# STM32F407VG.net
KiCad netlist of a schematic drawn in Altium Designer
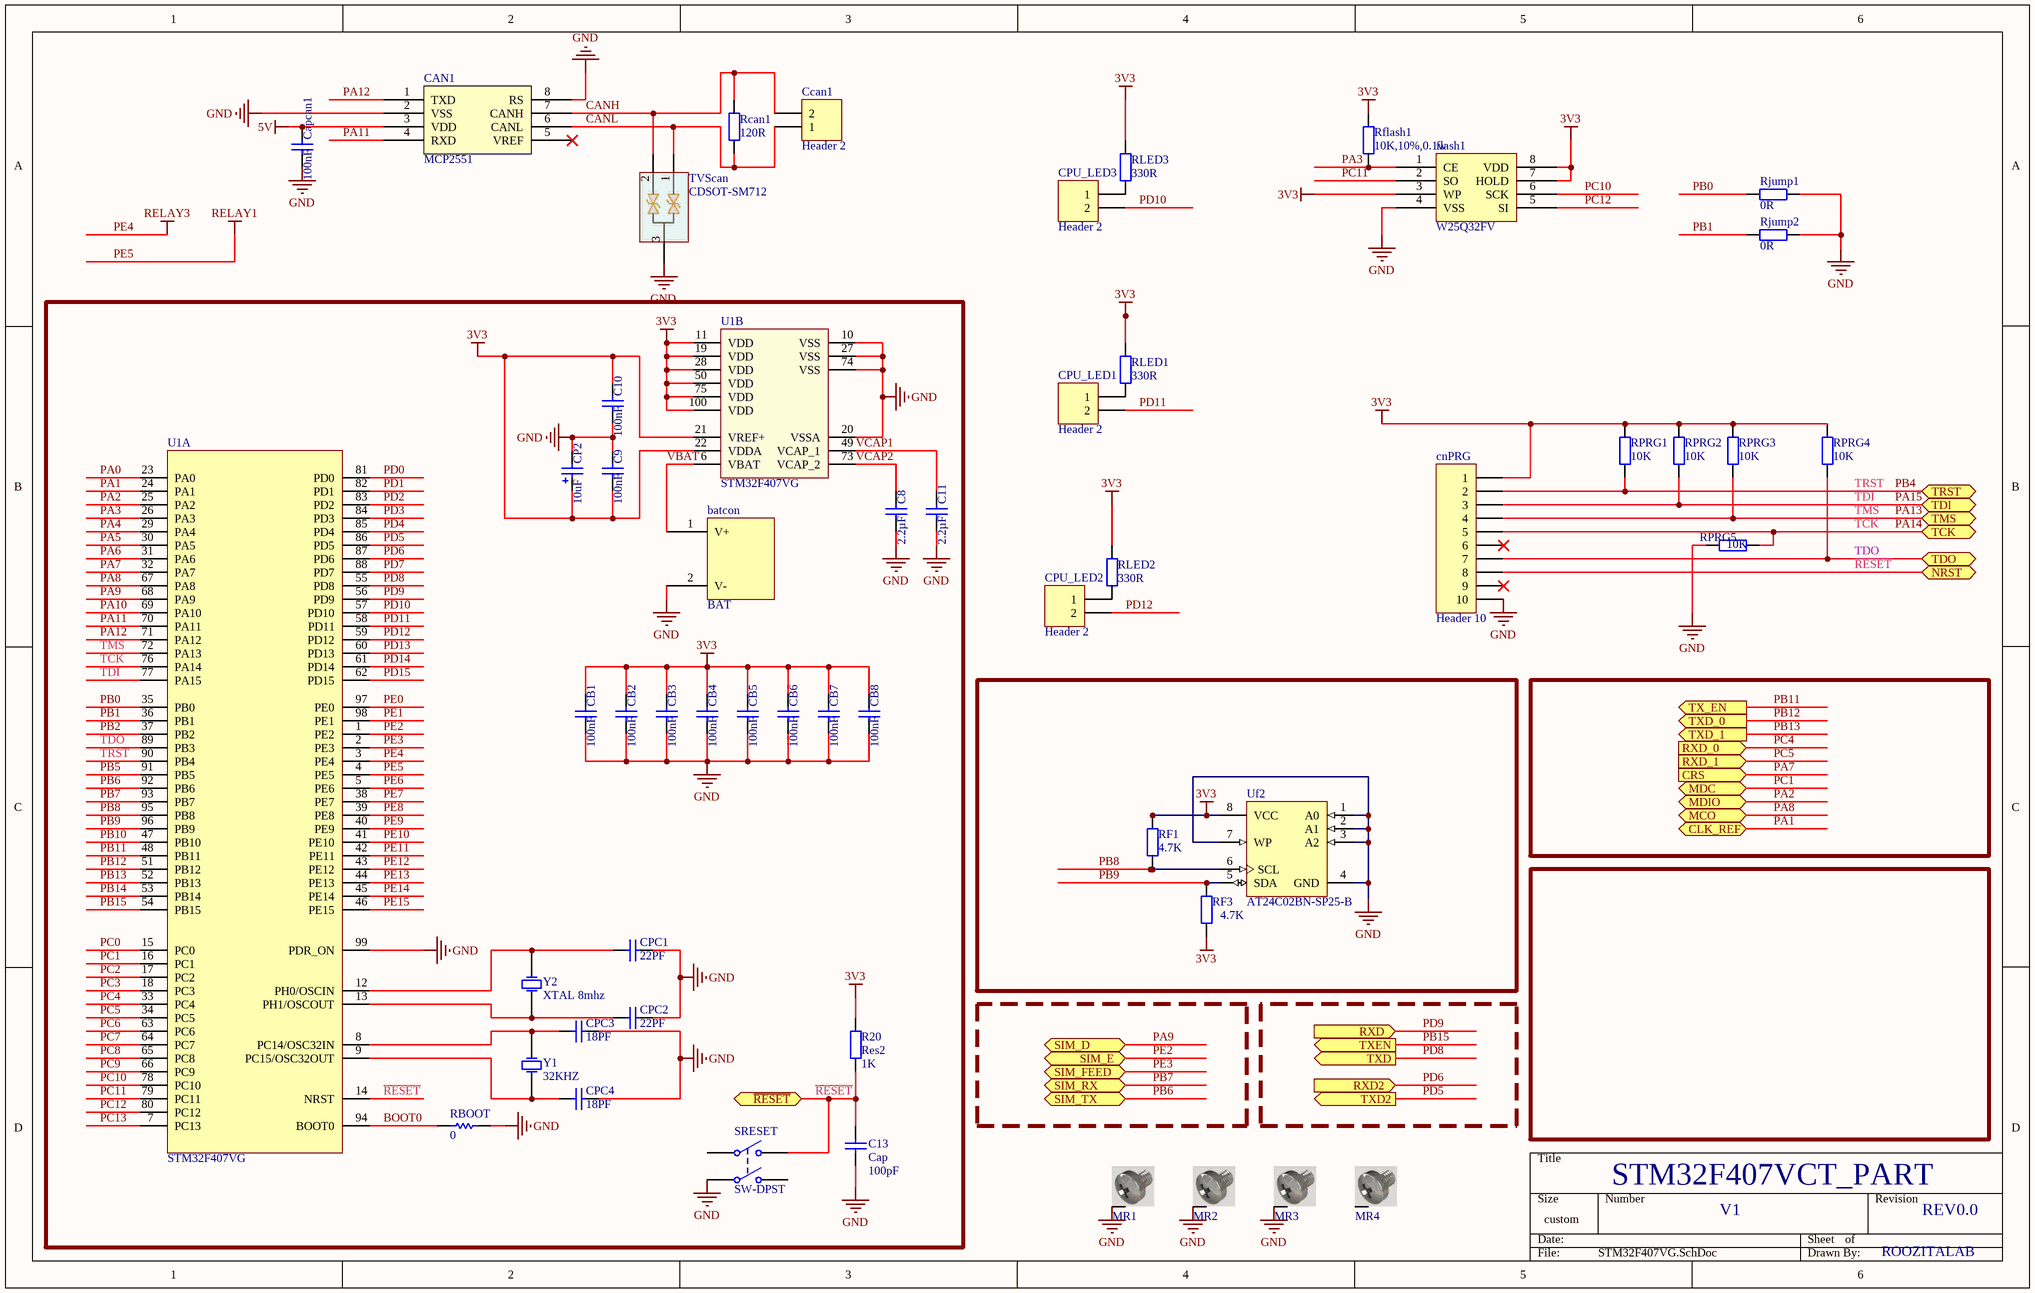
[diagram p0: STM32F407VG.SchDoc]

(export (version "E")
  (design (tool "Eeschema 10.0.6"))
  (components
    (comp (ref "batcon") (value "BAT") (footprint "BATTERY") (libsource (lib "my dxp lib") (part "BAT")))
    (comp (ref "C8")
      (value "2.2µF")
      (footprint "0805.")
      (description "Capacitor")
      (fields (field (name "PUBLISHER") "Altium Limited"))
      (libsource (lib "STM32F407_144") (part "Cap"))
    )
    (comp (ref "C9")
      (value "100nF")
      (footprint "0805.")
      (description "Capacitor")
      (fields (field (name "PUBLISHER") "Altium Limited"))
      (libsource (lib "STM32F407_144") (part "Cap"))
    )
    (comp (ref "C10")
      (value "100nF")
      (footprint "0805.")
      (description "Capacitor")
      (fields (field (name "PUBLISHER") "Altium Limited"))
      (libsource (lib "STM32F407_144") (part "Cap"))
    )
    (comp (ref "C11")
      (value "2.2µF")
      (footprint "0805.")
      (description "Capacitor")
      (fields (field (name "PUBLISHER") "Altium Limited"))
      (libsource (lib "STM32F407_144") (part "Cap"))
    )
    (comp (ref "C13")
      (value "Cap")
      (footprint "0805.")
      (description "Capacitor")
      (fields (field (name "ALTIUM_VALUE") "100pF") (field (name "PUBLISHER") "Altium Limited"))
      (libsource (lib "Miscellaneous Devices") (part "Cap"))
    )
    (comp (ref "CAN1")
      (value "MCP2551")
      (footprint "SOIC8")
      (libsource (lib "PCB_Project1") (part "SN65VHD230"))
    )
    (comp (ref "Capcan1")
      (value "100nF")
      (footprint "0805.")
      (description "Capacitor")
      (fields (field (name "PUBLISHER") "Altium Limited"))
      (libsource (lib "STM32F407_144") (part "Cap"))
    )
    (comp (ref "CB1")
      (value "100nF")
      (footprint "0805.")
      (description "Capacitor")
      (fields (field (name "PUBLISHER") "Altium Limited"))
      (libsource (lib "STM32F407_144") (part "Cap"))
    )
    (comp (ref "CB2")
      (value "100nF")
      (footprint "0805.")
      (description "Capacitor")
      (fields (field (name "PUBLISHER") "Altium Limited"))
      (libsource (lib "STM32F407_144") (part "Cap"))
    )
    (comp (ref "CB3")
      (value "100nF")
      (footprint "0805.")
      (description "Capacitor")
      (fields (field (name "PUBLISHER") "Altium Limited"))
      (libsource (lib "STM32F407_144") (part "Cap"))
    )
    (comp (ref "CB4")
      (value "100nF")
      (footprint "0805.")
      (description "Capacitor")
      (fields (field (name "PUBLISHER") "Altium Limited"))
      (libsource (lib "STM32F407_144") (part "Cap"))
    )
    (comp (ref "CB5")
      (value "100nF")
      (footprint "0805.")
      (description "Capacitor")
      (fields (field (name "PUBLISHER") "Altium Limited"))
      (libsource (lib "STM32F407_144") (part "Cap"))
    )
    (comp (ref "CB6")
      (value "100nF")
      (footprint "0805.")
      (description "Capacitor")
      (fields (field (name "PUBLISHER") "Altium Limited"))
      (libsource (lib "STM32F407_144") (part "Cap"))
    )
    (comp (ref "CB7")
      (value "100nF")
      (footprint "0805.")
      (description "Capacitor")
      (fields (field (name "PUBLISHER") "Altium Limited"))
      (libsource (lib "STM32F407_144") (part "Cap"))
    )
    (comp (ref "CB8")
      (value "100nF")
      (footprint "0805.")
      (description "Capacitor")
      (fields (field (name "PUBLISHER") "Altium Limited"))
      (libsource (lib "STM32F407_144") (part "Cap"))
    )
    (comp (ref "Ccan1")
      (value "Header 2")
      (footprint "HDR1X2")
      (description "Header, 2-Pin")
      (fields (field (name "PUBLISHER") "Altium Limited"))
      (libsource (lib "") (part "Header 2_1"))
    )
    (comp (ref "cnPRG")
      (value "Header 10")
      (footprint "HDR1X10")
      (description "Header, 10-Pin")
      (fields (field (name "PUBLISHER") "Altium Limited"))
      (libsource (lib "Miscellaneous Connectors") (part "Header 10"))
    )
    (comp (ref "CP2")
      (value "10uF")
      (footprint "C1206.")
      (description "Polarized Capacitor (Radial)")
      (fields (field (name "PUBLISHER") "Altium Limited"))
      (libsource (lib "STM32F407_144") (part "Cap Pol1"))
    )
    (comp (ref "CPC1")
      (value "22PF")
      (footprint "0805.")
      (description "Capacitor")
      (fields (field (name "PUBLISHER") "Altium Limited"))
      (libsource (lib "STM32F407VG") (part "Cap"))
    )
    (comp (ref "CPC2")
      (value "22PF")
      (footprint "0805.")
      (description "Capacitor")
      (fields (field (name "PUBLISHER") "Altium Limited"))
      (libsource (lib "STM32F407VG") (part "Cap"))
    )
    (comp (ref "CPC3")
      (value "18PF")
      (footprint "0805.")
      (description "Capacitor")
      (fields (field (name "PUBLISHER") "Altium Limited"))
      (libsource (lib "STM32F407VG") (part "Cap"))
    )
    (comp (ref "CPC4")
      (value "18PF")
      (footprint "0805.")
      (description "Capacitor")
      (fields (field (name "PUBLISHER") "Altium Limited"))
      (libsource (lib "STM32F407VG") (part "Cap"))
    )
    (comp (ref "CPU_LED1")
      (value "Header 2")
      (footprint "HDR1X2")
      (description "Header, 2-Pin")
      (fields (field (name "PUBLISHER") "Altium Limited"))
      (libsource (lib "Miscellaneous Connectors") (part "Header 2"))
    )
    (comp (ref "CPU_LED2")
      (value "Header 2")
      (footprint "HDR1X2")
      (description "Header, 2-Pin")
      (fields (field (name "PUBLISHER") "Altium Limited"))
      (libsource (lib "Miscellaneous Connectors") (part "Header 2"))
    )
    (comp (ref "CPU_LED3")
      (value "Header 2")
      (footprint "HDR1X2")
      (description "Header, 2-Pin")
      (fields (field (name "PUBLISHER") "Altium Limited"))
      (libsource (lib "Miscellaneous Connectors") (part "Header 2"))
    )
    (comp (ref "flash1")
      (value "W25Q32FV")
      (footprint "SOIC8")
      (libsource (lib "PCB_Project1") (part "SST25"))
    )
    (comp (ref "MR1")
      (value "Screw")
      (footprint "Board Screw")
      (description "Board Screw With Spacer")
      (libsource (lib "My Library") (part "Board Screw"))
    )
    (comp (ref "MR2")
      (value "Screw")
      (footprint "Board Screw")
      (description "Board Screw With Spacer")
      (libsource (lib "My Library") (part "Board Screw"))
    )
    (comp (ref "MR3")
      (value "Screw")
      (footprint "Board Screw")
      (description "Board Screw With Spacer")
      (libsource (lib "My Library") (part "Board Screw"))
    )
    (comp (ref "MR4")
      (value "Screw")
      (footprint "Board Screw")
      (description "Board Screw With Spacer")
      (libsource (lib "My Library") (part "Board Screw"))
    )
    (comp (ref "R20")
      (value "Res2")
      (footprint "0805.")
      (description "Resistor")
      (fields (field (name "ALTIUM_VALUE") "1K") (field (name "PUBLISHER") "Altium Limited"))
      (libsource (lib "") (part "Res2_1"))
    )
    (comp (ref "RBOOT")
      (value "0")
      (footprint "0805.")
      (description "Resistor")
      (fields (field (name "PUBLISHER") "Altium Limited"))
      (libsource (lib "STM32F407_144") (part "Res1"))
    )
    (comp (ref "Rcan1")
      (value "120R")
      (footprint "0805.")
      (description "Resistor")
      (fields (field (name "Comment") "120R,10%,0.1w") (field (name "PUBLISHER") "Altium Limited"))
      (libsource (lib "MBIO-SCHPCB-MBFD-REV1") (part "Res2"))
    )
    (comp (ref "RF1")
      (value "4.7K")
      (footprint "0805.")
      (description "Resistor")
      (fields (field (name "Comment") "Res2") (field (name "PUBLISHER") "Altium Limited"))
      (libsource (lib "Miscellaneous Devices") (part "Res2"))
    )
    (comp (ref "RF3")
      (value "4.7K")
      (footprint "0805.")
      (description "Resistor")
      (fields (field (name "Comment") "Res2") (field (name "PUBLISHER") "Altium Limited"))
      (libsource (lib "Miscellaneous Devices") (part "Res2"))
    )
    (comp (ref "Rflash1")
      (value "10K,10%,0.1w")
      (footprint "0805.")
      (description "Resistor")
      (fields (field (name "PUBLISHER") "Altium Limited"))
      (libsource (lib "") (part "Res2_1"))
    )
    (comp (ref "Rjump1")
      (value "0R")
      (footprint "0805.")
      (description "Resistor")
      (fields (field (name "Comment") "10K,10%,0.1w") (field (name "PUBLISHER") "Altium Limited"))
      (libsource (lib "PCB_Project1") (part "Res2"))
    )
    (comp (ref "Rjump2")
      (value "0R")
      (footprint "0805.")
      (description "Resistor")
      (fields (field (name "Comment") "10K,10%,0.1w") (field (name "PUBLISHER") "Altium Limited"))
      (libsource (lib "PCB_Project1") (part "Res2"))
    )
    (comp (ref "RLED1")
      (value "330R")
      (footprint "0805.")
      (description "Resistor")
      (fields (field (name "Comment") "330R,10%,0.1w") (field (name "PUBLISHER") "Altium Limited"))
      (libsource (lib "MBIO-SCHPCB-MBFD-REV1") (part "Res2"))
    )
    (comp (ref "RLED2")
      (value "330R")
      (footprint "0805.")
      (description "Resistor")
      (fields (field (name "Comment") "330R,10%,0.1w") (field (name "PUBLISHER") "Altium Limited"))
      (libsource (lib "MBIO-SCHPCB-MBFD-REV1") (part "Res2"))
    )
    (comp (ref "RLED3")
      (value "330R")
      (footprint "0805.")
      (description "Resistor")
      (fields (field (name "Comment") "330R,10%,0.1w") (field (name "PUBLISHER") "Altium Limited"))
      (libsource (lib "MBIO-SCHPCB-MBFD-REV1") (part "Res2"))
    )
    (comp (ref "RPRG1")
      (value "10K")
      (footprint "0805.")
      (description "Resistor")
      (fields (field (name "Comment") "Res2") (field (name "PUBLISHER") "Altium Limited"))
      (libsource (lib "Miscellaneous Devices") (part "Res2"))
    )
    (comp (ref "RPRG2")
      (value "10K")
      (footprint "0805.")
      (description "Resistor")
      (fields (field (name "Comment") "Res2") (field (name "PUBLISHER") "Altium Limited"))
      (libsource (lib "Miscellaneous Devices") (part "Res2"))
    )
    (comp (ref "RPRG3")
      (value "10K")
      (footprint "0805.")
      (description "Resistor")
      (fields (field (name "Comment") "Res2") (field (name "PUBLISHER") "Altium Limited"))
      (libsource (lib "Miscellaneous Devices") (part "Res2"))
    )
    (comp (ref "RPRG4")
      (value "10K")
      (footprint "0805.")
      (description "Resistor")
      (fields (field (name "Comment") "Res2") (field (name "PUBLISHER") "Altium Limited"))
      (libsource (lib "Miscellaneous Devices") (part "Res2"))
    )
    (comp (ref "RPRG5")
      (value "10K")
      (footprint "0805.")
      (description "Resistor")
      (fields (field (name "Comment") "Res2") (field (name "PUBLISHER") "Altium Limited"))
      (libsource (lib "") (part "Res2_2"))
    )
    (comp (ref "SRESET")
      (value "SW-DPST")
      (footprint "B3FS_SWITCH")
      (description "Double-Pole, Single-Throw Switch")
      (fields (field (name "PUBLISHER") "Altium Limited"))
      (libsource (lib "Miscellaneous Devices") (part "SW-DPST"))
    )
    (comp (ref "TVScan")
      (value "CDSOT-SM712")
      (footprint "2N3906_SMD")
      (libsource (lib "my schem") (part "nup2105"))
    )
    (comp (ref "U1")
      (value "STM32F407VG")
      (footprint "stm32f107")
      (libsource (lib "my dxp lib") (part "STM32F407VG"))
    )
    (comp (ref "Uf2")
      (value "AT24C02BN-SP25-B")
      (footprint "SOP8")
      (fields (field (name "PUBLISHER") "Altium Limited"))
      (libsource (lib "Atmel Memory Serial EEPROM") (part "AT24C02BN-SP25-B"))
    )
    (comp (ref "Y1")
      (value "32KHZ")
      (footprint "XTAL-RTC-RA")
      (description "Crystal Oscillator")
      (fields (field (name "PUBLISHER") "Altium Limited"))
      (libsource (lib "alarm box") (part "XTAL_1"))
    )
    (comp (ref "Y2")
      (value "XTAL 8mhz")
      (footprint "XTAL Small")
      (description "Crystal Oscillator")
      (fields (field (name "PUBLISHER") "Altium Limited"))
      (libsource (lib "alarm box") (part "XTAL"))
    )
  )
  (nets
    (net (code "1") (name "/BOOT0") (class "Default")
      (node (ref "RBOOT") (pin "1") (pinfunction "1_1") (pintype "passive"))
      (node (ref "U1") (pin "94") (pinfunction "BOOT0_94") (pintype "passive"))
    )
    (net (code "2") (name "/CANH") (class "Default")
      (node (ref "CAN1") (pin "7") (pinfunction "CANH_7") (pintype "passive"))
      (node (ref "Ccan1") (pin "2") (pinfunction "2_2") (pintype "passive"))
      (node (ref "Rcan1") (pin "2") (pinfunction "2_2") (pintype "passive"))
      (node (ref "TVScan") (pin "2") (pinfunction "2_2") (pintype "passive"))
    )
    (net (code "3") (name "/CANL") (class "Default")
      (node (ref "CAN1") (pin "6") (pinfunction "CANL_6") (pintype "passive"))
      (node (ref "Ccan1") (pin "1") (pinfunction "1_1") (pintype "passive"))
      (node (ref "Rcan1") (pin "1") (pinfunction "1_1") (pintype "passive"))
      (node (ref "TVScan") (pin "1") (pinfunction "1_1") (pintype "passive"))
    )
    (net (code "4") (name "/PA0") (class "Default")
      (node (ref "U1") (pin "23") (pinfunction "PA0_23") (pintype "passive"))
    )
    (net (code "5") (name "/PA1") (class "Default")
      (node (ref "U1") (pin "24") (pinfunction "PA1_24") (pintype "passive"))
    )
    (net (code "6") (name "/PA2") (class "Default")
      (node (ref "U1") (pin "25") (pinfunction "PA2_25") (pintype "passive"))
    )
    (net (code "7") (name "/PA3") (class "Default")
      (node (ref "Rflash1") (pin "2") (pinfunction "2_2") (pintype "passive"))
      (node (ref "U1") (pin "26") (pinfunction "PA3_26") (pintype "passive"))
      (node (ref "flash1") (pin "1") (pinfunction "CE_1") (pintype "passive"))
    )
    (net (code "8") (name "/PA4") (class "Default")
      (node (ref "U1") (pin "29") (pinfunction "PA4_29") (pintype "passive"))
    )
    (net (code "9") (name "/PA5") (class "Default")
      (node (ref "U1") (pin "30") (pinfunction "PA5_30") (pintype "passive"))
    )
    (net (code "10") (name "/PA6") (class "Default")
      (node (ref "U1") (pin "31") (pinfunction "PA6_31") (pintype "passive"))
    )
    (net (code "11") (name "/PA7") (class "Default")
      (node (ref "U1") (pin "32") (pinfunction "PA7_32") (pintype "passive"))
    )
    (net (code "12") (name "/PA8") (class "Default")
      (node (ref "U1") (pin "67") (pinfunction "PA8_67") (pintype "passive"))
    )
    (net (code "13") (name "/PA9") (class "Default")
      (node (ref "U1") (pin "68") (pinfunction "PA9_68") (pintype "passive"))
    )
    (net (code "14") (name "/PA10") (class "Default")
      (node (ref "U1") (pin "69") (pinfunction "PA10_69") (pintype "passive"))
    )
    (net (code "15") (name "/PA11") (class "Default")
      (node (ref "CAN1") (pin "4") (pinfunction "RXD_4") (pintype "passive"))
      (node (ref "U1") (pin "70") (pinfunction "PA11_70") (pintype "passive"))
    )
    (net (code "16") (name "/PA12") (class "Default")
      (node (ref "CAN1") (pin "1") (pinfunction "TXD_1") (pintype "passive"))
      (node (ref "U1") (pin "71") (pinfunction "PA12_71") (pintype "passive"))
    )
    (net (code "17") (name "/PA13") (class "Default")
      (node (ref "RPRG3") (pin "2") (pinfunction "2_2") (pintype "passive"))
      (node (ref "U1") (pin "72") (pinfunction "PA13_72") (pintype "passive"))
      (node (ref "cnPRG") (pin "4") (pinfunction "4_4") (pintype "passive"))
    )
    (net (code "18") (name "/PA14") (class "Default")
      (node (ref "RPRG5") (pin "1") (pinfunction "1_1") (pintype "passive"))
      (node (ref "U1") (pin "76") (pinfunction "PA14_76") (pintype "passive"))
      (node (ref "cnPRG") (pin "5") (pinfunction "5_5") (pintype "passive"))
    )
    (net (code "19") (name "/PA15") (class "Default")
      (node (ref "RPRG2") (pin "2") (pinfunction "2_2") (pintype "passive"))
      (node (ref "U1") (pin "77") (pinfunction "PA15_77") (pintype "passive"))
      (node (ref "cnPRG") (pin "3") (pinfunction "3_3") (pintype "passive"))
    )
    (net (code "20") (name "/PB0") (class "Default")
      (node (ref "Rjump1") (pin "1") (pinfunction "1_1") (pintype "passive"))
      (node (ref "U1") (pin "35") (pinfunction "PB0_35") (pintype "passive"))
    )
    (net (code "21") (name "/PB1") (class "Default")
      (node (ref "Rjump2") (pin "1") (pinfunction "1_1") (pintype "passive"))
      (node (ref "U1") (pin "36") (pinfunction "PB1_36") (pintype "passive"))
    )
    (net (code "22") (name "/PB2") (class "Default")
      (node (ref "U1") (pin "37") (pinfunction "PB2_37") (pintype "passive"))
    )
    (net (code "23") (name "/PB4") (class "Default")
      (node (ref "RPRG1") (pin "2") (pinfunction "2_2") (pintype "passive"))
      (node (ref "U1") (pin "90") (pinfunction "PB4_90") (pintype "passive"))
      (node (ref "cnPRG") (pin "2") (pinfunction "2_2") (pintype "passive"))
    )
    (net (code "24") (name "/PB5") (class "Default")
      (node (ref "U1") (pin "91") (pinfunction "PB5_91") (pintype "passive"))
    )
    (net (code "25") (name "/PB6") (class "Default")
      (node (ref "U1") (pin "92") (pinfunction "PB6_92") (pintype "passive"))
    )
    (net (code "26") (name "/PB7") (class "Default")
      (node (ref "U1") (pin "93") (pinfunction "PB7_93") (pintype "passive"))
    )
    (net (code "27") (name "/PB8") (class "Default")
      (node (ref "RF1") (pin "2") (pinfunction "2_2") (pintype "passive"))
      (node (ref "U1") (pin "95") (pinfunction "PB8_95") (pintype "passive"))
      (node (ref "Uf2") (pin "6") (pinfunction "SCL_6") (pintype "input"))
    )
    (net (code "28") (name "/PB9") (class "Default")
      (node (ref "RF3") (pin "1") (pinfunction "1_1") (pintype "passive"))
      (node (ref "U1") (pin "96") (pinfunction "PB9_96") (pintype "passive"))
      (node (ref "Uf2") (pin "5") (pinfunction "SDA_5") (pintype "bidirectional"))
    )
    (net (code "29") (name "/PB10") (class "Default")
      (node (ref "U1") (pin "47") (pinfunction "PB10_47") (pintype "passive"))
    )
    (net (code "30") (name "/PB11") (class "Default")
      (node (ref "U1") (pin "48") (pinfunction "PB11_48") (pintype "passive"))
    )
    (net (code "31") (name "/PB12") (class "Default")
      (node (ref "U1") (pin "51") (pinfunction "PB12_51") (pintype "passive"))
    )
    (net (code "32") (name "/PB13") (class "Default")
      (node (ref "U1") (pin "52") (pinfunction "PB13_52") (pintype "passive"))
    )
    (net (code "33") (name "/PB14") (class "Default")
      (node (ref "U1") (pin "53") (pinfunction "PB14_53") (pintype "passive"))
    )
    (net (code "34") (name "/PB15") (class "Default")
      (node (ref "U1") (pin "54") (pinfunction "PB15_54") (pintype "passive"))
    )
    (net (code "35") (name "/PC0") (class "Default")
      (node (ref "U1") (pin "15") (pinfunction "PC0_15") (pintype "passive"))
    )
    (net (code "36") (name "/PC1") (class "Default")
      (node (ref "U1") (pin "16") (pinfunction "PC1_16") (pintype "passive"))
    )
    (net (code "37") (name "/PC2") (class "Default")
      (node (ref "U1") (pin "17") (pinfunction "PC2_17") (pintype "passive"))
    )
    (net (code "38") (name "/PC3") (class "Default")
      (node (ref "U1") (pin "18") (pinfunction "PC3_18") (pintype "passive"))
    )
    (net (code "39") (name "/PC4") (class "Default")
      (node (ref "U1") (pin "33") (pinfunction "PC4_33") (pintype "passive"))
    )
    (net (code "40") (name "/PC5") (class "Default")
      (node (ref "U1") (pin "34") (pinfunction "PC5_34") (pintype "passive"))
    )
    (net (code "41") (name "/PC6") (class "Default")
      (node (ref "U1") (pin "63") (pinfunction "PC6_63") (pintype "passive"))
    )
    (net (code "42") (name "/PC7") (class "Default")
      (node (ref "U1") (pin "64") (pinfunction "PC7_64") (pintype "passive"))
    )
    (net (code "43") (name "/PC8") (class "Default")
      (node (ref "U1") (pin "65") (pinfunction "PC8_65") (pintype "passive"))
    )
    (net (code "44") (name "/PC9") (class "Default")
      (node (ref "U1") (pin "66") (pinfunction "PC9_66") (pintype "passive"))
    )
    (net (code "45") (name "/PC10") (class "Default")
      (node (ref "U1") (pin "78") (pinfunction "PC10_78") (pintype "passive"))
      (node (ref "flash1") (pin "6") (pinfunction "SCK_6") (pintype "passive"))
    )
    (net (code "46") (name "/PC11") (class "Default")
      (node (ref "U1") (pin "79") (pinfunction "PC11_79") (pintype "passive"))
      (node (ref "flash1") (pin "2") (pinfunction "SO_2") (pintype "passive"))
    )
    (net (code "47") (name "/PC12") (class "Default")
      (node (ref "U1") (pin "80") (pinfunction "PC12_80") (pintype "passive"))
      (node (ref "flash1") (pin "5") (pinfunction "SI_5") (pintype "passive"))
    )
    (net (code "48") (name "/PC13") (class "Default")
      (node (ref "U1") (pin "7") (pinfunction "PC13_7") (pintype "passive"))
    )
    (net (code "49") (name "/PD0") (class "Default")
      (node (ref "U1") (pin "81") (pinfunction "PD0_81") (pintype "passive"))
    )
    (net (code "50") (name "/PD1") (class "Default")
      (node (ref "U1") (pin "82") (pinfunction "PD1_82") (pintype "passive"))
    )
    (net (code "51") (name "/PD2") (class "Default")
      (node (ref "U1") (pin "83") (pinfunction "PD2_83") (pintype "passive"))
    )
    (net (code "52") (name "/PD3") (class "Default")
      (node (ref "U1") (pin "84") (pinfunction "PD3_84") (pintype "passive"))
    )
    (net (code "53") (name "/PD4") (class "Default")
      (node (ref "U1") (pin "85") (pinfunction "PD4_85") (pintype "passive"))
    )
    (net (code "54") (name "/PD5") (class "Default")
      (node (ref "U1") (pin "86") (pinfunction "PD5_86") (pintype "passive"))
    )
    (net (code "55") (name "/PD6") (class "Default")
      (node (ref "U1") (pin "87") (pinfunction "PD6_87") (pintype "passive"))
    )
    (net (code "56") (name "/PD7") (class "Default")
      (node (ref "U1") (pin "88") (pinfunction "PD7_88") (pintype "passive"))
    )
    (net (code "57") (name "/PD8") (class "Default")
      (node (ref "U1") (pin "55") (pinfunction "PD8_55") (pintype "passive"))
    )
    (net (code "58") (name "/PD9") (class "Default")
      (node (ref "U1") (pin "56") (pinfunction "PD9_56") (pintype "passive"))
    )
    (net (code "59") (name "/PD10") (class "Default")
      (node (ref "CPU_LED3") (pin "2") (pinfunction "2_2") (pintype "passive"))
      (node (ref "U1") (pin "57") (pinfunction "PD10_57") (pintype "passive"))
    )
    (net (code "60") (name "/PD11") (class "Default")
      (node (ref "CPU_LED1") (pin "2") (pinfunction "2_2") (pintype "passive"))
      (node (ref "U1") (pin "58") (pinfunction "PD11_58") (pintype "passive"))
    )
    (net (code "61") (name "/PD12") (class "Default")
      (node (ref "CPU_LED2") (pin "2") (pinfunction "2_2") (pintype "passive"))
      (node (ref "U1") (pin "59") (pinfunction "PD12_59") (pintype "passive"))
    )
    (net (code "62") (name "/PD13") (class "Default")
      (node (ref "U1") (pin "60") (pinfunction "PD13_60") (pintype "passive"))
    )
    (net (code "63") (name "/PD14") (class "Default")
      (node (ref "U1") (pin "61") (pinfunction "PD14_61") (pintype "passive"))
    )
    (net (code "64") (name "/PD15") (class "Default")
      (node (ref "U1") (pin "62") (pinfunction "PD15_62") (pintype "passive"))
    )
    (net (code "65") (name "/PE0") (class "Default")
      (node (ref "U1") (pin "97") (pinfunction "PE0_97") (pintype "passive"))
    )
    (net (code "66") (name "/PE1") (class "Default")
      (node (ref "U1") (pin "98") (pinfunction "PE1_98") (pintype "passive"))
    )
    (net (code "67") (name "/PE2") (class "Default")
      (node (ref "U1") (pin "1") (pinfunction "PE2_1") (pintype "passive"))
    )
    (net (code "68") (name "/PE3") (class "Default")
      (node (ref "U1") (pin "2") (pinfunction "PE3_2") (pintype "passive"))
    )
    (net (code "69") (name "/PE6") (class "Default")
      (node (ref "U1") (pin "5") (pinfunction "PE6_5") (pintype "passive"))
    )
    (net (code "70") (name "/PE7") (class "Default")
      (node (ref "U1") (pin "38") (pinfunction "PE7_38") (pintype "passive"))
    )
    (net (code "71") (name "/PE8") (class "Default")
      (node (ref "U1") (pin "39") (pinfunction "PE8_39") (pintype "passive"))
    )
    (net (code "72") (name "/PE9") (class "Default")
      (node (ref "U1") (pin "40") (pinfunction "PE9_40") (pintype "passive"))
    )
    (net (code "73") (name "/PE10") (class "Default")
      (node (ref "U1") (pin "41") (pinfunction "PE10_41") (pintype "passive"))
    )
    (net (code "74") (name "/PE11") (class "Default")
      (node (ref "U1") (pin "42") (pinfunction "PE11_42") (pintype "passive"))
    )
    (net (code "75") (name "/PE12") (class "Default")
      (node (ref "U1") (pin "43") (pinfunction "PE12_43") (pintype "passive"))
    )
    (net (code "76") (name "/PE13") (class "Default")
      (node (ref "U1") (pin "44") (pinfunction "PE13_44") (pintype "passive"))
    )
    (net (code "77") (name "/PE14") (class "Default")
      (node (ref "U1") (pin "45") (pinfunction "PE14_45") (pintype "passive"))
    )
    (net (code "78") (name "/PE15") (class "Default")
      (node (ref "U1") (pin "46") (pinfunction "PE15_46") (pintype "passive"))
    )
    (net (code "79") (name "/TDO") (class "Default")
      (node (ref "RPRG4") (pin "2") (pinfunction "2_2") (pintype "passive"))
      (node (ref "U1") (pin "89") (pinfunction "PB3_89") (pintype "passive"))
      (node (ref "cnPRG") (pin "7") (pinfunction "7_7") (pintype "passive"))
    )
    (net (code "80") (name "/VBAT") (class "Default")
      (node (ref "U1") (pin "6") (pinfunction "VBAT_6") (pintype "passive"))
      (node (ref "batcon") (pin "1") (pinfunction "V+_1") (pintype "passive"))
    )
    (net (code "81") (name "/VCAP1") (class "Default")
      (node (ref "C11") (pin "2") (pinfunction "2_2") (pintype "passive"))
      (node (ref "U1") (pin "49") (pinfunction "VCAP_1_49") (pintype "passive"))
    )
    (net (code "82") (name "/VCAP2") (class "Default")
      (node (ref "C8") (pin "2") (pinfunction "2_2") (pintype "passive"))
      (node (ref "U1") (pin "73") (pinfunction "VCAP_2_73") (pintype "passive"))
    )
    (net (code "83") (name "/~{RESET}") (class "Default")
      (node (ref "C13") (pin "2") (pinfunction "2_2") (pintype "passive"))
      (node (ref "R20") (pin "1") (pinfunction "1_1") (pintype "passive"))
      (node (ref "SRESET") (pin "2") (pinfunction "NO1_2") (pintype "passive"))
      (node (ref "U1") (pin "14") (pinfunction "NRST_14") (pintype "passive"))
      (node (ref "cnPRG") (pin "8") (pinfunction "8_8") (pintype "passive"))
    )
    (net (code "84") (name "3V3") (class "Default")
      (node (ref "C10") (pin "2") (pinfunction "2_2") (pintype "passive"))
      (node (ref "C9") (pin "1") (pinfunction "1_1") (pintype "passive"))
      (node (ref "CB1") (pin "2") (pinfunction "2_2") (pintype "passive"))
      (node (ref "CB2") (pin "2") (pinfunction "2_2") (pintype "passive"))
      (node (ref "CB3") (pin "2") (pinfunction "2_2") (pintype "passive"))
      (node (ref "CB4") (pin "2") (pinfunction "2_2") (pintype "passive"))
      (node (ref "CB5") (pin "2") (pinfunction "2_2") (pintype "passive"))
      (node (ref "CB6") (pin "2") (pinfunction "2_2") (pintype "passive"))
      (node (ref "CB7") (pin "2") (pinfunction "2_2") (pintype "passive"))
      (node (ref "CB8") (pin "2") (pinfunction "2_2") (pintype "passive"))
      (node (ref "CP2") (pin "1") (pinfunction "1_1") (pintype "passive"))
      (node (ref "R20") (pin "2") (pinfunction "2_2") (pintype "passive"))
      (node (ref "RF1") (pin "1") (pinfunction "1_1") (pintype "passive"))
      (node (ref "RF3") (pin "2") (pinfunction "2_2") (pintype "passive"))
      (node (ref "RLED1") (pin "2") (pinfunction "2_2") (pintype "passive"))
      (node (ref "RLED2") (pin "2") (pinfunction "2_2") (pintype "passive"))
      (node (ref "RLED3") (pin "2") (pinfunction "2_2") (pintype "passive"))
      (node (ref "RPRG1") (pin "1") (pinfunction "1_1") (pintype "passive"))
      (node (ref "RPRG2") (pin "1") (pinfunction "1_1") (pintype "passive"))
      (node (ref "RPRG3") (pin "1") (pinfunction "1_1") (pintype "passive"))
      (node (ref "RPRG4") (pin "1") (pinfunction "1_1") (pintype "passive"))
      (node (ref "Rflash1") (pin "1") (pinfunction "1_1") (pintype "passive"))
      (node (ref "U1") (pin "100") (pinfunction "VDD_100") (pintype "passive"))
      (node (ref "U1") (pin "11") (pinfunction "VDD_11") (pintype "passive"))
      (node (ref "U1") (pin "19") (pinfunction "VDD_19") (pintype "passive"))
      (node (ref "U1") (pin "21") (pinfunction "VREF+_21") (pintype "passive"))
      (node (ref "U1") (pin "22") (pinfunction "VDDA_22") (pintype "passive"))
      (node (ref "U1") (pin "28") (pinfunction "VDD_28") (pintype "passive"))
      (node (ref "U1") (pin "50") (pinfunction "VDD_50") (pintype "passive"))
      (node (ref "U1") (pin "75") (pinfunction "VDD_75") (pintype "passive"))
      (node (ref "Uf2") (pin "8") (pinfunction "VCC_8") (pintype "power_in"))
      (node (ref "cnPRG") (pin "1") (pinfunction "1_1") (pintype "passive"))
      (node (ref "flash1") (pin "3") (pinfunction "WP_3") (pintype "passive"))
      (node (ref "flash1") (pin "7") (pinfunction "HOLD_7") (pintype "passive"))
      (node (ref "flash1") (pin "8") (pinfunction "VDD_8") (pintype "passive"))
    )
    (net (code "85") (name "5V") (class "Default")
      (node (ref "CAN1") (pin "3") (pinfunction "VDD_3") (pintype "passive"))
      (node (ref "Capcan1") (pin "2") (pinfunction "2_2") (pintype "passive"))
    )
    (net (code "86") (name "GND") (class "Default")
      (node (ref "C10") (pin "1") (pinfunction "1_1") (pintype "passive"))
      (node (ref "C11") (pin "1") (pinfunction "1_1") (pintype "passive"))
      (node (ref "C13") (pin "1") (pinfunction "1_1") (pintype "passive"))
      (node (ref "C8") (pin "1") (pinfunction "1_1") (pintype "passive"))
      (node (ref "C9") (pin "2") (pinfunction "2_2") (pintype "passive"))
      (node (ref "CAN1") (pin "2") (pinfunction "VSS_2") (pintype "passive"))
      (node (ref "CAN1") (pin "8") (pinfunction "RS_8") (pintype "passive"))
      (node (ref "CB1") (pin "1") (pinfunction "1_1") (pintype "passive"))
      (node (ref "CB2") (pin "1") (pinfunction "1_1") (pintype "passive"))
      (node (ref "CB3") (pin "1") (pinfunction "1_1") (pintype "passive"))
      (node (ref "CB4") (pin "1") (pinfunction "1_1") (pintype "passive"))
      (node (ref "CB5") (pin "1") (pinfunction "1_1") (pintype "passive"))
      (node (ref "CB6") (pin "1") (pinfunction "1_1") (pintype "passive"))
      (node (ref "CB7") (pin "1") (pinfunction "1_1") (pintype "passive"))
      (node (ref "CB8") (pin "1") (pinfunction "1_1") (pintype "passive"))
      (node (ref "CP2") (pin "2") (pinfunction "2_2") (pintype "passive"))
      (node (ref "CPC1") (pin "2") (pinfunction "2_2") (pintype "passive"))
      (node (ref "CPC2") (pin "2") (pinfunction "2_2") (pintype "passive"))
      (node (ref "CPC3") (pin "2") (pinfunction "2_2") (pintype "passive"))
      (node (ref "CPC4") (pin "2") (pinfunction "2_2") (pintype "passive"))
      (node (ref "Capcan1") (pin "1") (pinfunction "1_1") (pintype "passive"))
      (node (ref "MR1") (pin "S") (pinfunction "S_S") (pintype "passive"))
      (node (ref "MR2") (pin "S") (pinfunction "S_S") (pintype "passive"))
      (node (ref "MR3") (pin "S") (pinfunction "S_S") (pintype "passive"))
      (node (ref "RBOOT") (pin "2") (pinfunction "2_2") (pintype "passive"))
      (node (ref "RPRG5") (pin "2") (pinfunction "2_2") (pintype "passive"))
      (node (ref "Rjump1") (pin "2") (pinfunction "2_2") (pintype "passive"))
      (node (ref "Rjump2") (pin "2") (pinfunction "2_2") (pintype "passive"))
      (node (ref "SRESET") (pin "3") (pinfunction "COMMON2_3") (pintype "passive"))
      (node (ref "TVScan") (pin "3") (pinfunction "3_3") (pintype "passive"))
      (node (ref "U1") (pin "10") (pinfunction "VSS_10") (pintype "passive"))
      (node (ref "U1") (pin "20") (pinfunction "VSSA_20") (pintype "passive"))
      (node (ref "U1") (pin "27") (pinfunction "VSS_27") (pintype "passive"))
      (node (ref "U1") (pin "74") (pinfunction "VSS_74") (pintype "passive"))
      (node (ref "U1") (pin "99") (pinfunction "PDR_ON_99") (pintype "passive"))
      (node (ref "Uf2") (pin "1") (pinfunction "A0_1") (pintype "input"))
      (node (ref "Uf2") (pin "2") (pinfunction "A1_2") (pintype "input"))
      (node (ref "Uf2") (pin "3") (pinfunction "A2_3") (pintype "input"))
      (node (ref "Uf2") (pin "4") (pinfunction "GND_4") (pintype "power_in"))
      (node (ref "Uf2") (pin "7") (pinfunction "WP_7") (pintype "input"))
      (node (ref "batcon") (pin "2") (pinfunction "V-_2") (pintype "passive"))
      (node (ref "cnPRG") (pin "10") (pinfunction "10_10") (pintype "passive"))
      (node (ref "flash1") (pin "4") (pinfunction "VSS_4") (pintype "passive"))
    )
    (net (code "87") (name "Net-(CPU_LED1-Pad1)") (class "Default")
      (node (ref "CPU_LED1") (pin "1") (pinfunction "1_1") (pintype "passive"))
      (node (ref "RLED1") (pin "1") (pinfunction "1_1") (pintype "passive"))
    )
    (net (code "88") (name "Net-(CPU_LED2-Pad1)") (class "Default")
      (node (ref "CPU_LED2") (pin "1") (pinfunction "1_1") (pintype "passive"))
      (node (ref "RLED2") (pin "1") (pinfunction "1_1") (pintype "passive"))
    )
    (net (code "89") (name "Net-(CPU_LED3-Pad1)") (class "Default")
      (node (ref "CPU_LED3") (pin "1") (pinfunction "1_1") (pintype "passive"))
      (node (ref "RLED3") (pin "1") (pinfunction "1_1") (pintype "passive"))
    )
    (net (code "90") (name "Net-(U1A-PC14{slash}OSC32IN)") (class "Default")
      (node (ref "CPC3") (pin "1") (pinfunction "1_1") (pintype "passive"))
      (node (ref "U1") (pin "8") (pinfunction "PC14/OSC32IN_8") (pintype "passive"))
      (node (ref "Y1") (pin "2") (pinfunction "OSC2_2") (pintype "passive"))
    )
    (net (code "91") (name "Net-(U1A-PC15{slash}OSC32OUT)") (class "Default")
      (node (ref "CPC4") (pin "1") (pinfunction "1_1") (pintype "passive"))
      (node (ref "U1") (pin "9") (pinfunction "PC15/OSC32OUT_9") (pintype "passive"))
      (node (ref "Y1") (pin "1") (pinfunction "OSC1_1") (pintype "passive"))
    )
    (net (code "92") (name "Net-(U1A-PH0{slash}OSCIN)") (class "Default")
      (node (ref "CPC1") (pin "1") (pinfunction "1_1") (pintype "passive"))
      (node (ref "U1") (pin "12") (pinfunction "PH0/OSCIN_12") (pintype "passive"))
      (node (ref "Y2") (pin "2") (pinfunction "OSC2_2") (pintype "passive"))
    )
    (net (code "93") (name "Net-(U1A-PH1{slash}OSCOUT)") (class "Default")
      (node (ref "CPC2") (pin "1") (pinfunction "1_1") (pintype "passive"))
      (node (ref "U1") (pin "13") (pinfunction "PH1/OSCOUT_13") (pintype "passive"))
      (node (ref "Y2") (pin "1") (pinfunction "OSC1_1") (pintype "passive"))
    )
    (net (code "94") (name "RELAY1") (class "Default")
      (node (ref "U1") (pin "4") (pinfunction "PE5_4") (pintype "passive"))
    )
    (net (code "95") (name "RELAY3") (class "Default")
      (node (ref "U1") (pin "3") (pinfunction "PE4_3") (pintype "passive"))
    )
    (net (code "96") (name "unconnected-(CAN1-VREF-Pad5)") (class "Default")
      (node (ref "CAN1") (pin "5") (pinfunction "VREF_5") (pintype "passive+no_connect"))
    )
    (net (code "97") (name "unconnected-(MR4-PadS)") (class "Default")
      (node (ref "MR4") (pin "S") (pinfunction "S_S") (pintype "passive"))
    )
    (net (code "98") (name "unconnected-(SRESET-COMMON1-Pad1)") (class "Default")
      (node (ref "SRESET") (pin "1") (pinfunction "COMMON1_1") (pintype "passive"))
    )
    (net (code "99") (name "unconnected-(SRESET-NO2-Pad4)") (class "Default")
      (node (ref "SRESET") (pin "4") (pinfunction "NO2_4") (pintype "passive"))
    )
    (net (code "100") (name "unconnected-(cnPRG-Pad6)") (class "Default")
      (node (ref "cnPRG") (pin "6") (pinfunction "6_6") (pintype "passive+no_connect"))
    )
    (net (code "101") (name "unconnected-(cnPRG-Pad9)") (class "Default")
      (node (ref "cnPRG") (pin "9") (pinfunction "9_9") (pintype "passive+no_connect"))
    )
  )
)
